# pebble_qi_eagle.net
KiCad netlist of a schematic drawn in EAGLE
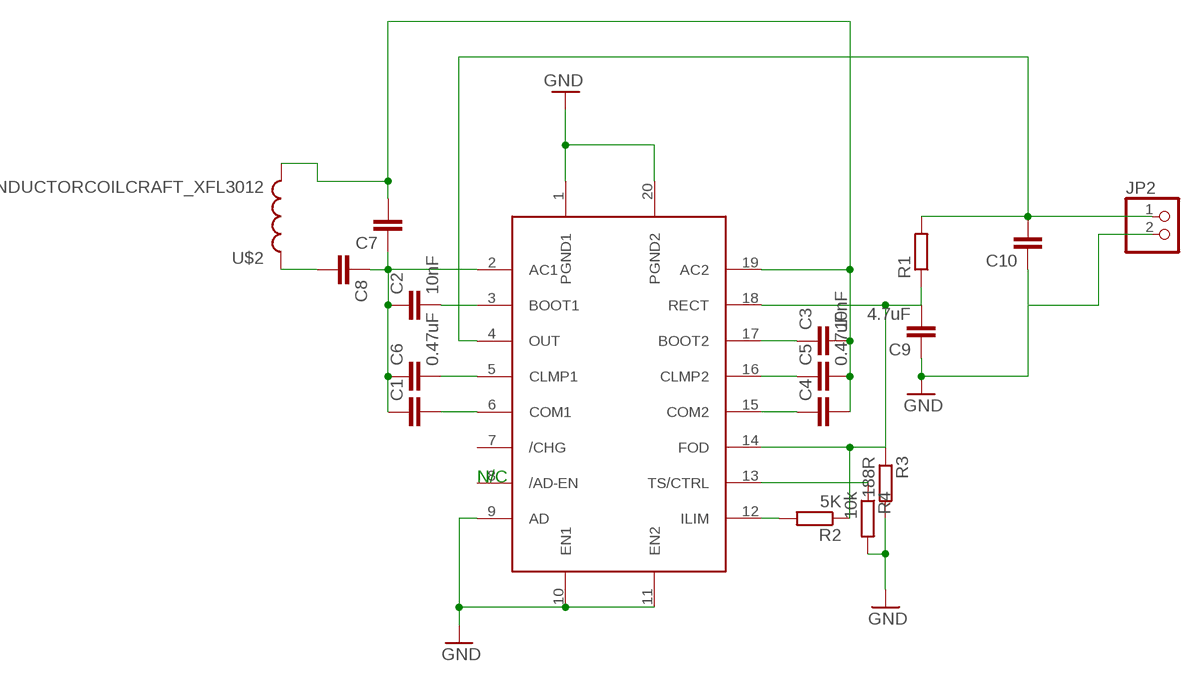
[diagram p0: schematic, sheet 1]

(export (version "E")
  (design (tool "Eeschema 10.0.6"))
  (components
    (comp (ref "C1")
      (value "C-EUC0603")
      (footprint "eagle-import:C0603")
      (libsource (lib "eagle-import") (part "C-EUC0603"))
    )
    (comp (ref "C2")
      (value "10nF")
      (footprint "eagle-import:C0603")
      (libsource (lib "eagle-import") (part "resistor_C-EUC0603"))
    )
    (comp (ref "C3")
      (value "10nF")
      (footprint "eagle-import:C0603")
      (libsource (lib "eagle-import") (part "C-EUC0603"))
    )
    (comp (ref "C4")
      (value "C-EUC0603")
      (footprint "eagle-import:C0603")
      (libsource (lib "eagle-import") (part "C-EUC0603"))
    )
    (comp (ref "C5")
      (value "0.47uF")
      (footprint "eagle-import:C0603")
      (libsource (lib "eagle-import") (part "C-EUC0603"))
    )
    (comp (ref "C6")
      (value "0.47uF")
      (footprint "eagle-import:C0603")
      (libsource (lib "eagle-import") (part "C-EUC0603"))
    )
    (comp (ref "C7")
      (value "C-EUC0603")
      (footprint "eagle-import:C0603")
      (libsource (lib "eagle-import") (part "C-EUC0603"))
    )
    (comp (ref "C8")
      (value "C-EUC0603")
      (footprint "eagle-import:C0603")
      (libsource (lib "eagle-import") (part "C-EUC0603"))
    )
    (comp (ref "C9")
      (value "4.7uF")
      (footprint "eagle-import:C0603")
      (libsource (lib "eagle-import") (part "C-EUC0603"))
    )
    (comp (ref "C10")
      (value "C-EUC0603")
      (footprint "eagle-import:C0603")
      (libsource (lib "eagle-import") (part "C-EUC0603"))
    )
    (comp (ref "JP2")
      (value "PINHD-1X2/90")
      (footprint "eagle-import:1X02_90")
      (libsource (lib "eagle-import") (part "PINHD-1X2/90"))
    )
    (comp (ref "R1")
      (value "R-EU_R0603")
      (footprint "eagle-import:R0603")
      (libsource (lib "eagle-import") (part "R-EU_R0603"))
    )
    (comp (ref "R2")
      (value "5K")
      (footprint "eagle-import:R0603")
      (libsource (lib "eagle-import") (part "R-EU_R0603"))
    )
    (comp (ref "R3")
      (value "188R")
      (footprint "eagle-import:R0603")
      (libsource (lib "eagle-import") (part "R-EU_R0603"))
    )
    (comp (ref "R4")
      (value "10k")
      (footprint "eagle-import:R0603")
      (libsource (lib "eagle-import") (part "R-EU_R0603"))
    )
    (comp (ref "U$1")
      (value "BQ51013B")
      (footprint "eagle-import:QFNRHL20")
      (libsource (lib "eagle-import") (part "BQ51013B"))
    )
    (comp (ref "U$2")
      (value "INDUCTORCOILCRAFT_XFL3012")
      (footprint "eagle-import:COILCRAFT_XFL3012")
      (libsource (lib "eagle-import") (part "INDUCTORCOILCRAFT_XFL3012"))
    )
  )
  (nets
    (net (code "1") (name "GND") (class "Default")
      (node (ref "C10") (pin "1") (pinfunction "1_1") (pintype "passive"))
      (node (ref "C9") (pin "1") (pinfunction "1_1") (pintype "passive"))
      (node (ref "JP2") (pin "2") (pinfunction "2_2") (pintype "passive"))
      (node (ref "R3") (pin "2") (pinfunction "2_2") (pintype "passive"))
      (node (ref "R4") (pin "2") (pinfunction "2_2") (pintype "passive"))
      (node (ref "U$1") (pin "1") (pinfunction "PGND1_1") (pintype "power_in"))
      (node (ref "U$1") (pin "10") (pinfunction "EN1_10") (pintype "bidirectional"))
      (node (ref "U$1") (pin "11") (pinfunction "EN2_11") (pintype "bidirectional"))
      (node (ref "U$1") (pin "20") (pinfunction "PGND2_20") (pintype "power_in"))
      (node (ref "U$1") (pin "9") (pinfunction "AD_9") (pintype "bidirectional"))
    )
    (net (code "2") (name "Net-(U$1-AC1)") (class "Default")
      (node (ref "C1") (pin "1") (pinfunction "1_1") (pintype "passive"))
      (node (ref "C2") (pin "1") (pinfunction "1_1") (pintype "passive"))
      (node (ref "C6") (pin "1") (pinfunction "1_1") (pintype "passive"))
      (node (ref "C7") (pin "1") (pinfunction "1_1") (pintype "passive"))
      (node (ref "C8") (pin "1") (pinfunction "1_1") (pintype "passive"))
      (node (ref "U$1") (pin "2") (pinfunction "AC1_2") (pintype "bidirectional"))
    )
    (net (code "3") (name "Net-(U$1-AC2)") (class "Default")
      (node (ref "C3") (pin "2") (pinfunction "2_2") (pintype "passive"))
      (node (ref "C4") (pin "2") (pinfunction "2_2") (pintype "passive"))
      (node (ref "C5") (pin "2") (pinfunction "2_2") (pintype "passive"))
      (node (ref "C7") (pin "2") (pinfunction "2_2") (pintype "passive"))
      (node (ref "U$1") (pin "19") (pinfunction "AC2_19") (pintype "bidirectional"))
      (node (ref "U$2") (pin "P$2") (pinfunction "2_P$2") (pintype "passive"))
    )
    (net (code "4") (name "Net-(U$1-BOOT1)") (class "Default")
      (node (ref "C2") (pin "2") (pinfunction "2_2") (pintype "passive"))
      (node (ref "U$1") (pin "3") (pinfunction "BOOT1_3") (pintype "bidirectional"))
    )
    (net (code "5") (name "Net-(U$1-BOOT2)") (class "Default")
      (node (ref "C3") (pin "1") (pinfunction "1_1") (pintype "passive"))
      (node (ref "U$1") (pin "17") (pinfunction "BOOT2_17") (pintype "bidirectional"))
    )
    (net (code "6") (name "Net-(U$1-CLMP1)") (class "Default")
      (node (ref "C6") (pin "2") (pinfunction "2_2") (pintype "passive"))
      (node (ref "U$1") (pin "5") (pinfunction "CLMP1_5") (pintype "bidirectional"))
    )
    (net (code "7") (name "Net-(U$1-CLMP2)") (class "Default")
      (node (ref "C5") (pin "1") (pinfunction "1_1") (pintype "passive"))
      (node (ref "U$1") (pin "16") (pinfunction "CLMP2_16") (pintype "bidirectional"))
    )
    (net (code "8") (name "Net-(U$1-COM1)") (class "Default")
      (node (ref "C1") (pin "2") (pinfunction "2_2") (pintype "passive"))
      (node (ref "U$1") (pin "6") (pinfunction "COM1_6") (pintype "bidirectional"))
    )
    (net (code "9") (name "Net-(U$1-COM2)") (class "Default")
      (node (ref "C4") (pin "1") (pinfunction "1_1") (pintype "passive"))
      (node (ref "U$1") (pin "15") (pinfunction "COM2_15") (pintype "bidirectional"))
    )
    (net (code "10") (name "Net-(U$1-FOD)") (class "Default")
      (node (ref "C9") (pin "2") (pinfunction "2_2") (pintype "passive"))
      (node (ref "R1") (pin "1") (pinfunction "1_1") (pintype "passive"))
      (node (ref "R2") (pin "1") (pinfunction "1_1") (pintype "passive"))
      (node (ref "R3") (pin "1") (pinfunction "1_1") (pintype "passive"))
      (node (ref "U$1") (pin "14") (pinfunction "FOD_14") (pintype "bidirectional"))
      (node (ref "U$1") (pin "18") (pinfunction "RECT_18") (pintype "bidirectional"))
    )
    (net (code "11") (name "Net-(U$1-ILIM)") (class "Default")
      (node (ref "R2") (pin "2") (pinfunction "2_2") (pintype "passive"))
      (node (ref "U$1") (pin "12") (pinfunction "ILIM_12") (pintype "bidirectional"))
    )
    (net (code "12") (name "Net-(U$1-OUT)") (class "Default")
      (node (ref "C10") (pin "2") (pinfunction "2_2") (pintype "passive"))
      (node (ref "JP2") (pin "1") (pinfunction "1_1") (pintype "passive"))
      (node (ref "R1") (pin "2") (pinfunction "2_2") (pintype "passive"))
      (node (ref "U$1") (pin "4") (pinfunction "OUT_4") (pintype "bidirectional"))
    )
    (net (code "13") (name "Net-(U$1-TS{slash}CTRL)") (class "Default")
      (node (ref "R4") (pin "1") (pinfunction "1_1") (pintype "passive"))
      (node (ref "U$1") (pin "13") (pinfunction "TS/CTRL_13") (pintype "bidirectional"))
    )
    (net (code "14") (name "Net-(U$2-1)") (class "Default")
      (node (ref "C8") (pin "2") (pinfunction "2_2") (pintype "passive"))
      (node (ref "U$2") (pin "P$1") (pinfunction "1_P$1") (pintype "passive"))
    )
    (net (code "15") (name "unconnected-(U$1-{slash}AD-EN-Pad8)") (class "Default")
      (node (ref "U$1") (pin "8") (pinfunction "/AD-EN_8") (pintype "bidirectional"))
    )
    (net (code "16") (name "unconnected-(U$1-{slash}CHG-Pad7)") (class "Default")
      (node (ref "U$1") (pin "7") (pinfunction "/CHG_7") (pintype "bidirectional"))
    )
  )
)
